# SERIALIO.net
KiCad netlist of a schematic drawn in Altium Designer
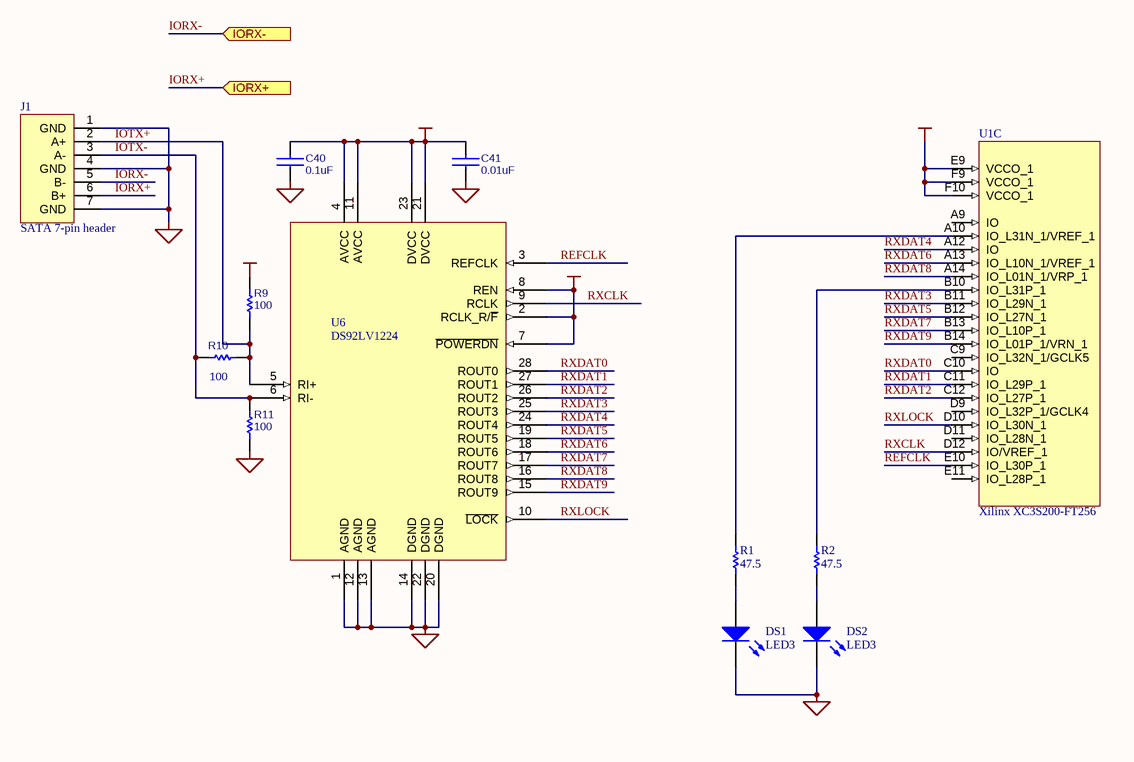
[diagram p0: SERIALIO.SCHDOC]

(export (version "E")
  (design (tool "Eeschema 10.0.6"))
  (components
    (comp (ref "C40")
      (value "0.1uF")
      (footprint "0603")
      (description "Standard Capacitor")
      (fields (field (name "Comment") "CAPACITOR"))
      (libsource (lib "parts") (part "CAPACITOR"))
    )
    (comp (ref "C41")
      (value "0.01uF")
      (footprint "0402")
      (description "Standard Capacitor")
      (fields (field (name "Comment") "CAPACITOR"))
      (libsource (lib "parts") (part "CAPACITOR"))
    )
    (comp (ref "DS1")
      (value "LED3")
      (footprint "SMD _LED")
      (description "Typical BLUE SiC LED")
      (fields (field (name "PUBLISHER") "Altium Limited"))
      (libsource (lib "Miscellaneous Devices") (part "LED3"))
    )
    (comp (ref "DS2")
      (value "LED3")
      (footprint "SMD _LED")
      (description "Typical BLUE SiC LED")
      (fields (field (name "PUBLISHER") "Altium Limited"))
      (libsource (lib "Miscellaneous Devices") (part "LED3"))
    )
    (comp (ref "J1")
      (value "SATA 7-pin header")
      (footprint "MOLES 67800-5005")
      (libsource (lib "parts") (part "SATA-7"))
    )
    (comp (ref "R1")
      (value "47.5")
      (footprint "0603")
      (description "Standard Passive Resistor")
      (fields (field (name "Comment") "current-limiting series res"))
      (libsource (lib "parts") (part "RESISTOR"))
    )
    (comp (ref "R2")
      (value "47.5")
      (footprint "0603")
      (description "Standard Passive Resistor")
      (fields (field (name "Comment") "current-limiting series res"))
      (libsource (lib "parts") (part "RESISTOR"))
    )
    (comp (ref "R9")
      (value "100")
      (footprint "0603")
      (description "Standard Passive Resistor")
      (libsource (lib "parts") (part "RESISTOR"))
    )
    (comp (ref "R10")
      (value "100")
      (footprint "0603")
      (description "Standard Passive Resistor")
      (libsource (lib "parts") (part "RESISTOR"))
    )
    (comp (ref "R11")
      (value "100")
      (footprint "0603")
      (description "Standard Passive Resistor")
      (libsource (lib "parts") (part "RESISTOR"))
    )
    (comp (ref "U1")
      (value "Xilinx XC3S200-FT256")
      (footprint "Xilinx FT256 BGA")
      (description "Xilinx Spartan-3 FPGA")
      (libsource (lib "parts") (part "XC3S200-FT256"))
    )
    (comp (ref "U6")
      (value "DS92LV1224")
      (footprint "SSO-G28/E4.3")
      (description "30-66 MHz 10-Bit Bus LVDS Deserializer")
      (libsource (lib "parts") (part "DS92LV1224"))
    )
  )
  (nets
    (net (code "1") (name "/IORX+") (class "Default")
      (node (ref "J1") (pin "6") (pinfunction "B+_6") (pintype "passive"))
    )
    (net (code "2") (name "/IORX-") (class "Default")
      (node (ref "J1") (pin "5") (pinfunction "B-_5") (pintype "passive"))
    )
    (net (code "3") (name "/IOTX+") (class "Default")
      (node (ref "J1") (pin "2") (pinfunction "A+_2") (pintype "passive"))
      (node (ref "R10") (pin "2") (pintype "passive"))
      (node (ref "R9") (pin "2") (pintype "passive"))
      (node (ref "U6") (pin "5") (pinfunction "RI+_5") (pintype "input"))
    )
    (net (code "4") (name "/IOTX-") (class "Default")
      (node (ref "J1") (pin "3") (pinfunction "A-_3") (pintype "passive"))
      (node (ref "R10") (pin "1") (pintype "passive"))
      (node (ref "R11") (pin "2") (pintype "passive"))
      (node (ref "U6") (pin "6") (pinfunction "RI-_6") (pintype "input"))
    )
    (net (code "5") (name "/REFCLK") (class "Default")
      (node (ref "U1") (pin "E10") (pinfunction "IO_L30P_1_E10") (pintype "input"))
      (node (ref "U6") (pin "3") (pinfunction "REFCLK_3") (pintype "input"))
    )
    (net (code "6") (name "/RXCLK") (class "Default")
      (node (ref "U1") (pin "D12") (pinfunction "IO/VREF_1_D12") (pintype "input"))
      (node (ref "U6") (pin "9") (pinfunction "RCLK_9") (pintype "output"))
    )
    (net (code "7") (name "/RXDAT0") (class "Default")
      (node (ref "U1") (pin "C10") (pinfunction "IO_C10") (pintype "input"))
      (node (ref "U6") (pin "28") (pinfunction "ROUT0_28") (pintype "output"))
    )
    (net (code "8") (name "/RXDAT1") (class "Default")
      (node (ref "U1") (pin "C11") (pinfunction "IO_L29P_1_C11") (pintype "input"))
      (node (ref "U6") (pin "27") (pinfunction "ROUT1_27") (pintype "output"))
    )
    (net (code "9") (name "/RXDAT2") (class "Default")
      (node (ref "U1") (pin "C12") (pinfunction "IO_L27P_1_C12") (pintype "input"))
      (node (ref "U6") (pin "26") (pinfunction "ROUT2_26") (pintype "output"))
    )
    (net (code "10") (name "/RXDAT3") (class "Default")
      (node (ref "U1") (pin "B11") (pinfunction "IO_L29N_1_B11") (pintype "input"))
      (node (ref "U6") (pin "25") (pinfunction "ROUT3_25") (pintype "output"))
    )
    (net (code "11") (name "/RXDAT4") (class "Default")
      (node (ref "U1") (pin "A12") (pinfunction "IO_A12") (pintype "input"))
      (node (ref "U6") (pin "24") (pinfunction "ROUT4_24") (pintype "output"))
    )
    (net (code "12") (name "/RXDAT5") (class "Default")
      (node (ref "U1") (pin "B12") (pinfunction "IO_L27N_1_B12") (pintype "input"))
      (node (ref "U6") (pin "19") (pinfunction "ROUT5_19") (pintype "output"))
    )
    (net (code "13") (name "/RXDAT6") (class "Default")
      (node (ref "U1") (pin "A13") (pinfunction "IO_L10N_1/VREF_1_A13") (pintype "input"))
      (node (ref "U6") (pin "18") (pinfunction "ROUT6_18") (pintype "output"))
    )
    (net (code "14") (name "/RXDAT7") (class "Default")
      (node (ref "U1") (pin "B13") (pinfunction "IO_L10P_1_B13") (pintype "input"))
      (node (ref "U6") (pin "17") (pinfunction "ROUT7_17") (pintype "output"))
    )
    (net (code "15") (name "/RXDAT8") (class "Default")
      (node (ref "U1") (pin "A14") (pinfunction "IO_L01N_1/VRP_1_A14") (pintype "input"))
      (node (ref "U6") (pin "16") (pinfunction "ROUT8_16") (pintype "output"))
    )
    (net (code "16") (name "/RXDAT9") (class "Default")
      (node (ref "U1") (pin "B14") (pinfunction "IO_L01P_1/VRN_1_B14") (pintype "input"))
      (node (ref "U6") (pin "15") (pinfunction "ROUT9_15") (pintype "output"))
    )
    (net (code "17") (name "/RXLOCK") (class "Default")
      (node (ref "U1") (pin "D10") (pinfunction "IO_L30N_1_D10") (pintype "input"))
      (node (ref "U6") (pin "10") (pinfunction "~{LOCK}_10") (pintype "output"))
    )
    (net (code "18") (name "GND") (class "Default")
      (node (ref "C40") (pin "1") (pintype "passive"))
      (node (ref "C41") (pin "1") (pintype "passive"))
      (node (ref "DS1") (pin "2") (pinfunction "K_2") (pintype "passive"))
      (node (ref "DS2") (pin "2") (pinfunction "K_2") (pintype "passive"))
      (node (ref "J1") (pin "1") (pinfunction "GND_1") (pintype "passive"))
      (node (ref "J1") (pin "4") (pinfunction "GND_4") (pintype "passive"))
      (node (ref "J1") (pin "7") (pinfunction "GND_7") (pintype "passive"))
      (node (ref "R11") (pin "1") (pintype "passive"))
      (node (ref "U6") (pin "1") (pinfunction "AGND_1") (pintype "power_in"))
      (node (ref "U6") (pin "12") (pinfunction "AGND_12") (pintype "power_in"))
      (node (ref "U6") (pin "13") (pinfunction "AGND_13") (pintype "power_in"))
      (node (ref "U6") (pin "14") (pinfunction "DGND_14") (pintype "power_in"))
      (node (ref "U6") (pin "20") (pinfunction "DGND_20") (pintype "power_in"))
      (node (ref "U6") (pin "22") (pinfunction "DGND_22") (pintype "power_in"))
    )
    (net (code "19") (name "Net-(DS1-A)") (class "Default")
      (node (ref "DS1") (pin "1") (pinfunction "A_1") (pintype "passive"))
      (node (ref "R1") (pin "2") (pintype "passive"))
    )
    (net (code "20") (name "Net-(DS2-A)") (class "Default")
      (node (ref "DS2") (pin "1") (pinfunction "A_1") (pintype "passive"))
      (node (ref "R2") (pin "2") (pintype "passive"))
    )
    (net (code "21") (name "Net-(U1C-IO_L31N_1{slash}VREF_1)") (class "Default")
      (node (ref "R1") (pin "1") (pintype "passive"))
      (node (ref "U1") (pin "A10") (pinfunction "IO_L31N_1/VREF_1_A10") (pintype "input"))
    )
    (net (code "22") (name "Net-(U1C-IO_L31P_1)") (class "Default")
      (node (ref "R2") (pin "1") (pintype "passive"))
      (node (ref "U1") (pin "B10") (pinfunction "IO_L31P_1_B10") (pintype "input"))
    )
    (net (code "23") (name "VCC") (class "Default")
      (node (ref "C40") (pin "2") (pintype "passive"))
      (node (ref "C41") (pin "2") (pintype "passive"))
      (node (ref "R9") (pin "1") (pintype "passive"))
      (node (ref "U1") (pin "E9") (pinfunction "VCCO_1_E9") (pintype "input"))
      (node (ref "U1") (pin "F10") (pinfunction "VCCO_1_F10") (pintype "input"))
      (node (ref "U1") (pin "F9") (pinfunction "VCCO_1_F9") (pintype "input"))
      (node (ref "U6") (pin "11") (pinfunction "AVCC_11") (pintype "power_in"))
      (node (ref "U6") (pin "2") (pinfunction "RCLK_R/~{F}_2") (pintype "output"))
      (node (ref "U6") (pin "21") (pinfunction "DVCC_21") (pintype "power_in"))
      (node (ref "U6") (pin "23") (pinfunction "DVCC_23") (pintype "power_in"))
      (node (ref "U6") (pin "4") (pinfunction "AVCC_4") (pintype "power_in"))
      (node (ref "U6") (pin "7") (pinfunction "~{POWERDN}_7") (pintype "input"))
      (node (ref "U6") (pin "8") (pinfunction "REN_8") (pintype "input"))
    )
    (net (code "24") (name "unconnected-(U1C-IO-PadA9)") (class "Default")
      (node (ref "U1") (pin "A9") (pinfunction "IO_A9") (pintype "input"))
    )
    (net (code "25") (name "unconnected-(U1C-IO_L28N_1-PadD11)") (class "Default")
      (node (ref "U1") (pin "D11") (pinfunction "IO_L28N_1_D11") (pintype "input"))
    )
    (net (code "26") (name "unconnected-(U1C-IO_L28P_1-PadE11)") (class "Default")
      (node (ref "U1") (pin "E11") (pinfunction "IO_L28P_1_E11") (pintype "input"))
    )
    (net (code "27") (name "unconnected-(U1C-IO_L32N_1{slash}GCLK5-PadC9)") (class "Default")
      (node (ref "U1") (pin "C9") (pinfunction "IO_L32N_1/GCLK5_C9") (pintype "input"))
    )
    (net (code "28") (name "unconnected-(U1C-IO_L32P_1{slash}GCLK4-PadD9)") (class "Default")
      (node (ref "U1") (pin "D9") (pinfunction "IO_L32P_1/GCLK4_D9") (pintype "input"))
    )
  )
)
